# CCM_0019.net
KiCad netlist of a schematic drawn in EAGLE
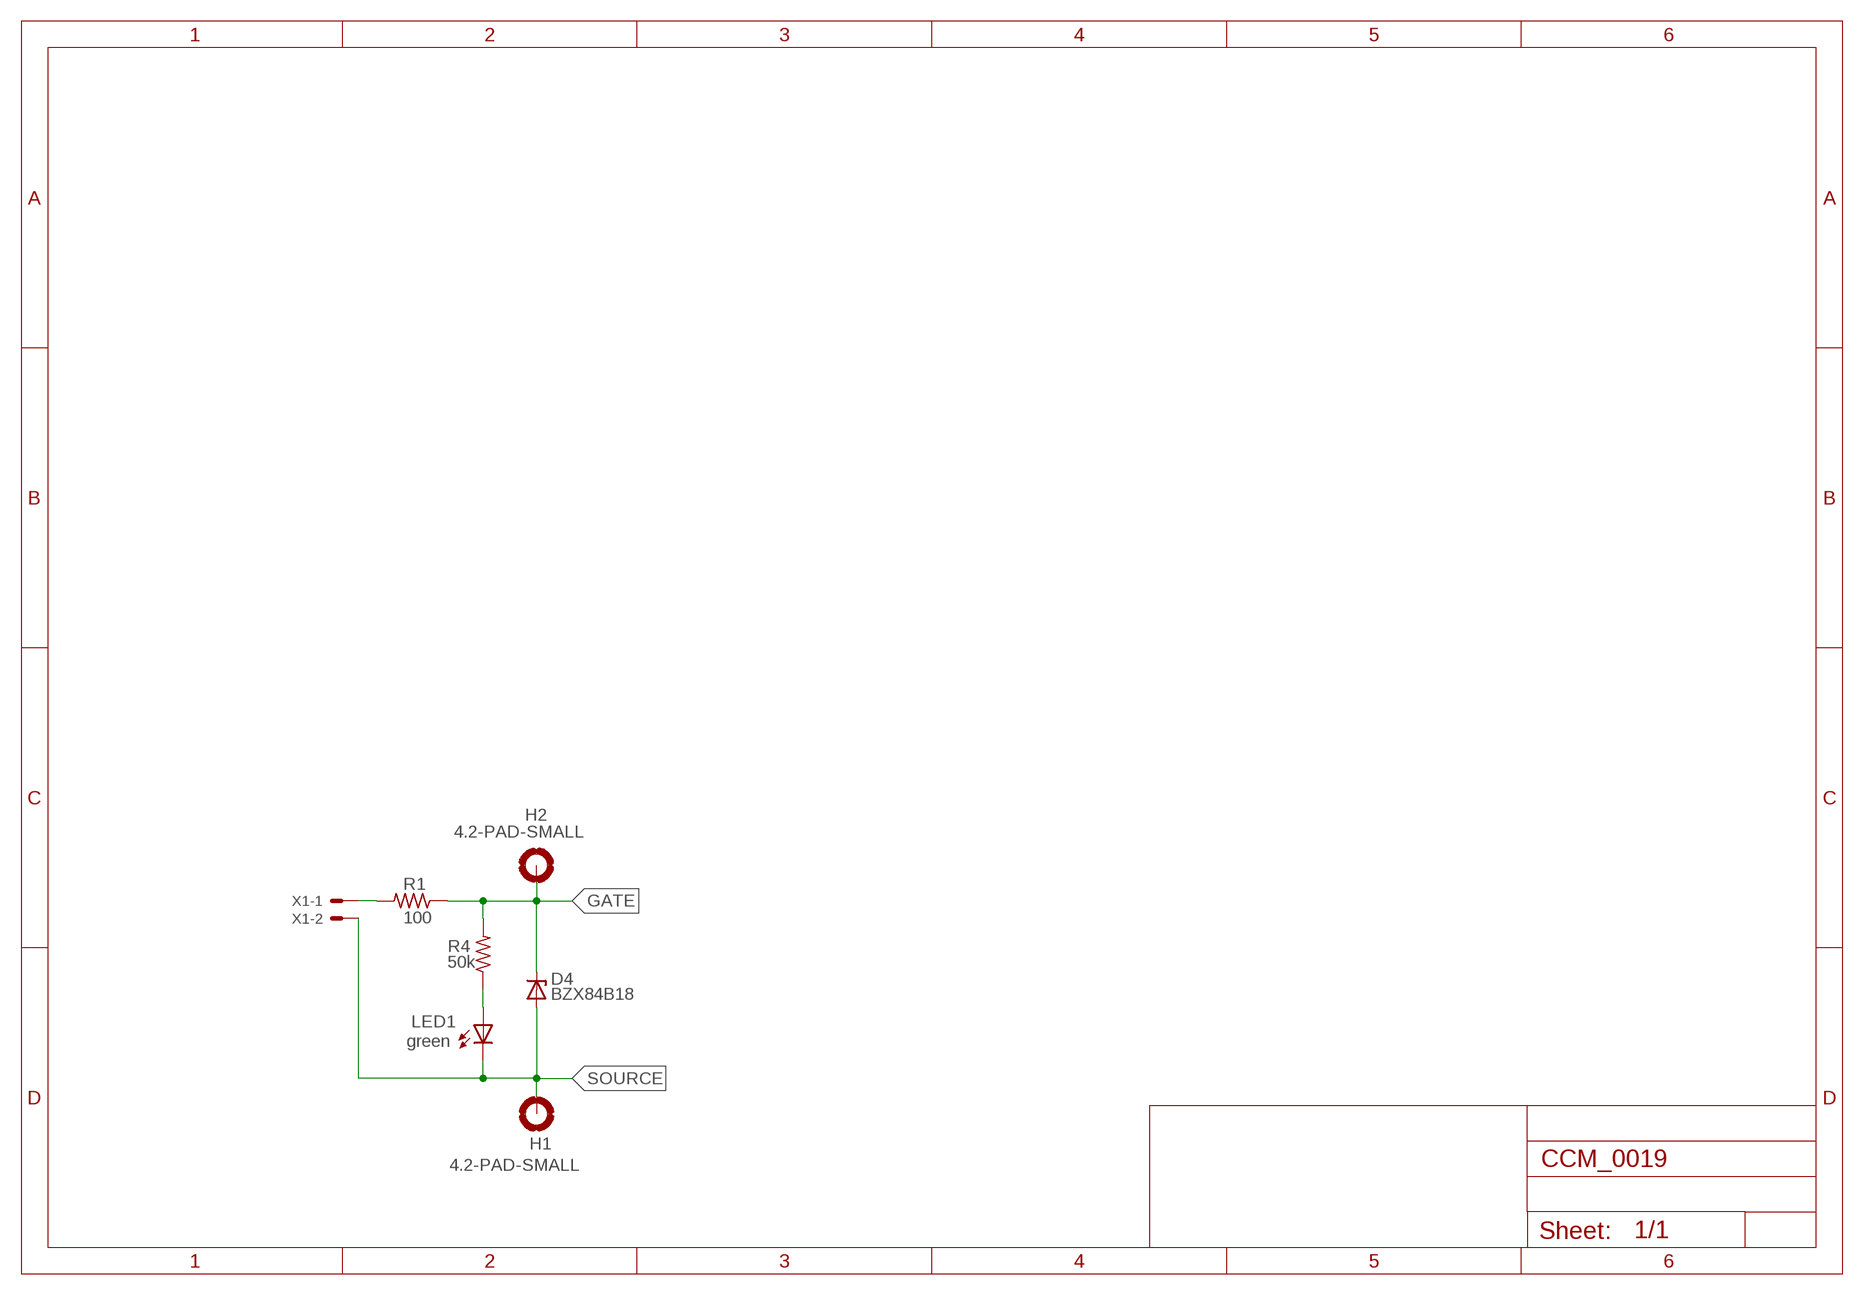
[diagram p0: schematic, sheet 1]

(export (version "E")
  (design (tool "Eeschema 10.0.6"))
  (components
    (comp (ref "D4")
      (value "BZX84B18")
      (footprint "eagle-import:SOT23")
      (libsource (lib "eagle-import") (part "ZENER-DIODESOT23"))
    )
    (comp (ref "H1")
      (value "4.2-PAD-SMALL")
      (footprint "eagle-import:4.2-PAD-SMALL")
      (libsource (lib "eagle-import") (part "4.2-PAD-SMALL"))
    )
    (comp (ref "H2")
      (value "4.2-PAD-SMALL")
      (footprint "eagle-import:4.2-PAD-SMALL")
      (libsource (lib "eagle-import") (part "4.2-PAD-SMALL"))
    )
    (comp (ref "LED1")
      (value "green")
      (footprint "eagle-import:CHIPLED_0603")
      (libsource (lib "eagle-import") (part "LEDCHIPLED_0603"))
    )
    (comp (ref "R1")
      (value "100")
      (footprint "eagle-import:0603")
      (libsource (lib "eagle-import") (part "RESISTOR0603"))
    )
    (comp (ref "R4")
      (value "50k")
      (footprint "eagle-import:0603")
      (libsource (lib "eagle-import") (part "RESISTOR0603"))
    )
    (comp (ref "X1")
      (value "22-23-2021")
      (footprint "eagle-import:22-23-2021")
      (fields (field (name "MF") "MOLEX"))
      (libsource (lib "eagle-import") (part "22-23-2021"))
    )
  )
  (nets
    (net (code "1") (name "GATE") (class "Default")
      (node (ref "D4") (pin "3") (pinfunction "C_3") (pintype "passive"))
      (node (ref "H2") (pin "B4,2") (pinfunction "MOUNT_B4,2") (pintype "passive"))
      (node (ref "R1") (pin "1") (pinfunction "1_1") (pintype "passive"))
      (node (ref "R4") (pin "2") (pinfunction "2_2") (pintype "passive"))
    )
    (net (code "2") (name "Net-(LED1-PadA)") (class "Default")
      (node (ref "LED1") (pin "A") (pinfunction "A_A") (pintype "passive"))
      (node (ref "R4") (pin "1") (pinfunction "1_1") (pintype "passive"))
    )
    (net (code "3") (name "Net-(X1A-S)") (class "Default")
      (node (ref "R1") (pin "2") (pinfunction "2_2") (pintype "passive"))
      (node (ref "X1") (pin "1") (pinfunction "S_1") (pintype "passive"))
    )
    (net (code "4") (name "SOURCE") (class "Default")
      (node (ref "D4") (pin "1") (pinfunction "A_1") (pintype "passive"))
      (node (ref "H1") (pin "B4,2") (pinfunction "MOUNT_B4,2") (pintype "passive"))
      (node (ref "LED1") (pin "C") (pinfunction "C_C") (pintype "passive"))
      (node (ref "X1") (pin "2") (pinfunction "S_2") (pintype "passive"))
    )
  )
)
